# 3_ADC.net
KiCad netlist of a schematic drawn in Altium Designer
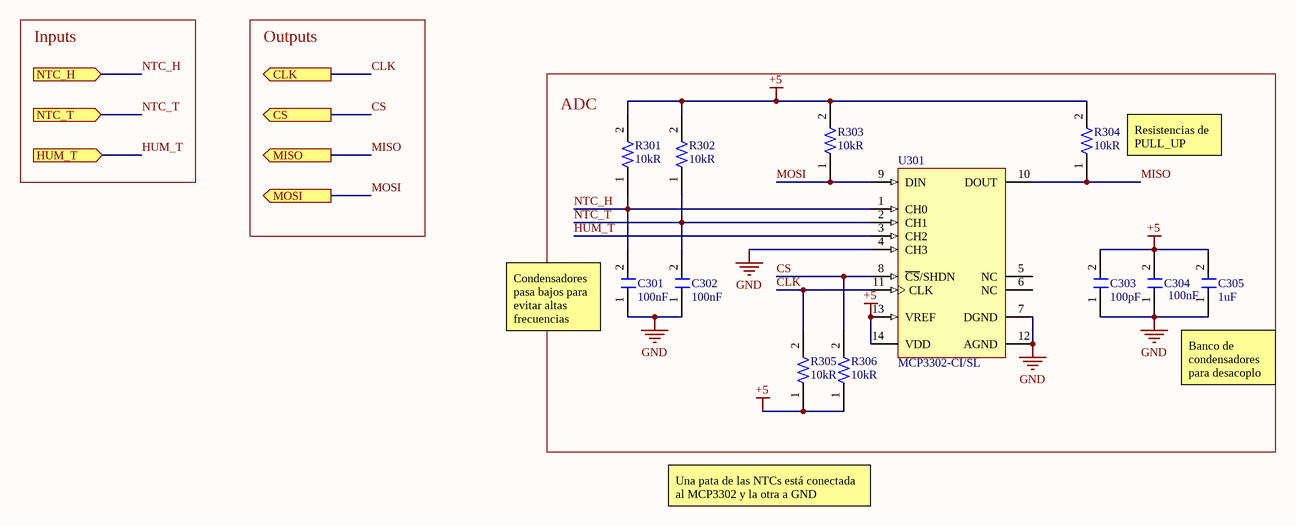
[diagram p0: [3] ADC.SchDoc]

(export (version "E")
  (design (tool "Eeschema 10.0.6"))
  (components
    (comp (ref "C301")
      (value "885012208058")
      (footprint "C1206FNPC-RW")
      (description "Cap Cer 0.1UF 25V X7R 1206")
      (fields
        (field (name "MANUFACTURER") "Wurth Electronics")
        (field (name "TOLERANCE") "10%")
        (field (name "CAPACITANCE") "100nF")
        (field (name ".CREATOR") "DO")
      )
      (libsource (lib "Passives") (part "C100n-25V-1206FNPC-X7R"))
    )
    (comp (ref "C302")
      (value "885012208058")
      (footprint "C1206FNPC-RW")
      (description "Cap Cer 0.1UF 25V X7R 1206")
      (fields
        (field (name "MANUFACTURER") "Wurth Electronics")
        (field (name "TOLERANCE") "10%")
        (field (name "CAPACITANCE") "100nF")
        (field (name ".CREATOR") "DO")
      )
      (libsource (lib "Passives") (part "C100n-25V-1206FNPC-X7R"))
    )
    (comp (ref "C303")
      (value "885012007057")
      (footprint "C0805FNPC-W")
      (fields
        (field (name "MANUFACTURER") "Wurth Electronics")
        (field (name "TOLERANCE") "5%")
        (field (name "CAPACITANCE") "100pF")
        (field (name ".CREATOR") "DR")
      )
      (libsource (lib "Passives") (part "C100p-50V-0805FNPC-C0G/NP0"))
    )
    (comp (ref "C304")
      (value "885012208058")
      (footprint "C1206FNPC-RW")
      (description "Cap Cer 0.1UF 25V X7R 1206")
      (fields
        (field (name "MANUFACTURER") "Wurth Electronics")
        (field (name "TOLERANCE") "10%")
        (field (name "CAPACITANCE") "100nF")
        (field (name ".CREATOR") "DO")
      )
      (libsource (lib "Passives") (part "C100n-25V-1206FNPC-X7R"))
    )
    (comp (ref "C305")
      (value "885012208036")
      (footprint "C1206FNPC-RW")
      (description "Cap Cer 1UF 16V X7R 1206")
      (fields
        (field (name "MANUFACTURER") "Wurth Electronics")
        (field (name "TOLERANCE") "10%")
        (field (name "CAPACITANCE") "1uF")
        (field (name ".CREATOR") "GP")
      )
      (libsource (lib "Passives") (part "C1u-16V-1206FNPC-X7R"))
    )
    (comp (ref "R301")
      (value "CRCW120610K0FKEA")
      (footprint "R1206FTK-W")
      (description "Res Thick Film 1206 10K Ohm 1% 0.25W(1/4W) +/-100ppm/ßC Pad SMD Automotive T/R")
      (fields (field (name "RESISTANCE") "10kR") (field (name ".CREATOR") "GP"))
      (libsource (lib "Passives") (part "R10k-1206FTK"))
    )
    (comp (ref "R302")
      (value "CRCW120610K0FKEA")
      (footprint "R1206FTK-W")
      (description "Res Thick Film 1206 10K Ohm 1% 0.25W(1/4W) +/-100ppm/ßC Pad SMD Automotive T/R")
      (fields (field (name "RESISTANCE") "10kR") (field (name ".CREATOR") "GP"))
      (libsource (lib "Passives") (part "R10k-1206FTK"))
    )
    (comp (ref "R303")
      (value "CRCW120610K0FKEA")
      (footprint "R1206FTK-W")
      (description "Res Thick Film 1206 10K Ohm 1% 0.25W(1/4W) +/-100ppm/ßC Pad SMD Automotive T/R")
      (fields (field (name "RESISTANCE") "10kR") (field (name ".CREATOR") "GP"))
      (libsource (lib "Passives") (part "R10k-1206FTK"))
    )
    (comp (ref "R304")
      (value "CRCW120610K0FKEA")
      (footprint "R1206FTK-W")
      (description "Res Thick Film 1206 10K Ohm 1% 0.25W(1/4W) +/-100ppm/ßC Pad SMD Automotive T/R")
      (fields (field (name "RESISTANCE") "10kR") (field (name ".CREATOR") "GP"))
      (libsource (lib "Passives") (part "R10k-1206FTK"))
    )
    (comp (ref "R305")
      (value "CRCW120610K0FKEA")
      (footprint "R1206FTK-W")
      (description "Res Thick Film 1206 10K Ohm 1% 0.25W(1/4W) +/-100ppm/ßC Pad SMD Automotive T/R")
      (fields (field (name "RESISTANCE") "10kR") (field (name ".CREATOR") "GP"))
      (libsource (lib "Passives") (part "R10k-1206FTK"))
    )
    (comp (ref "R306")
      (value "CRCW120610K0FKEA")
      (footprint "R1206FTK-W")
      (description "Res Thick Film 1206 10K Ohm 1% 0.25W(1/4W) +/-100ppm/ßC Pad SMD Automotive T/R")
      (fields (field (name "RESISTANCE") "10kR") (field (name ".CREATOR") "GP"))
      (libsource (lib "Passives") (part "R10k-1206FTK"))
    )
    (comp (ref "U301")
      (value "MCP3302-CI/SL")
      (footprint "SOIC-SL14_L")
      (description "ADC, Successive Approximation, 13-Bit, 1 Func, 4 Channel, Serial Access, PDSO14")
      (libsource (lib "EMEA- E-Tech Racing- I'Escola d'Enginyeria de Barcelona Est") (part "CON-ADC-MCP3004-14"))
    )
  )
  (nets
    (net (code "1") (name "+5") (class "Default")
      (node (ref "C303") (pin "2") (pinfunction "2_2") (pintype "passive"))
      (node (ref "C304") (pin "2") (pinfunction "2_2") (pintype "passive"))
      (node (ref "C305") (pin "2") (pinfunction "2_2") (pintype "passive"))
      (node (ref "R301") (pin "2") (pinfunction "2_2") (pintype "passive"))
      (node (ref "R302") (pin "2") (pinfunction "2_2") (pintype "passive"))
      (node (ref "R303") (pin "2") (pinfunction "2_2") (pintype "passive"))
      (node (ref "R304") (pin "2") (pinfunction "2_2") (pintype "passive"))
      (node (ref "R305") (pin "1") (pinfunction "1_1") (pintype "passive"))
      (node (ref "R306") (pin "1") (pinfunction "1_1") (pintype "passive"))
      (node (ref "U301") (pin "13") (pinfunction "VREF_13") (pintype "input"))
      (node (ref "U301") (pin "14") (pinfunction "VDD_14") (pintype "power_in"))
    )
    (net (code "2") (name "/CLK") (class "Default")
      (node (ref "R305") (pin "2") (pinfunction "2_2") (pintype "passive"))
      (node (ref "U301") (pin "11") (pinfunction "CLK_11") (pintype "input"))
    )
    (net (code "3") (name "/CS") (class "Default")
      (node (ref "R306") (pin "2") (pinfunction "2_2") (pintype "passive"))
      (node (ref "U301") (pin "8") (pinfunction "~{CS}/SHDN_8") (pintype "input"))
    )
    (net (code "4") (name "/HUM_T") (class "Default")
      (node (ref "U301") (pin "3") (pinfunction "CH2_3") (pintype "input"))
    )
    (net (code "5") (name "/MISO") (class "Default")
      (node (ref "R304") (pin "1") (pinfunction "1_1") (pintype "passive"))
      (node (ref "U301") (pin "10") (pinfunction "DOUT_10") (pintype "tri_state"))
    )
    (net (code "6") (name "/MOSI") (class "Default")
      (node (ref "R303") (pin "1") (pinfunction "1_1") (pintype "passive"))
      (node (ref "U301") (pin "9") (pinfunction "DIN_9") (pintype "input"))
    )
    (net (code "7") (name "/NTC_H") (class "Default")
      (node (ref "C301") (pin "2") (pinfunction "2_2") (pintype "passive"))
      (node (ref "R301") (pin "1") (pinfunction "1_1") (pintype "passive"))
      (node (ref "U301") (pin "1") (pinfunction "CH0_1") (pintype "input"))
    )
    (net (code "8") (name "/NTC_T") (class "Default")
      (node (ref "C302") (pin "2") (pinfunction "2_2") (pintype "passive"))
      (node (ref "R302") (pin "1") (pinfunction "1_1") (pintype "passive"))
      (node (ref "U301") (pin "2") (pinfunction "CH1_2") (pintype "input"))
    )
    (net (code "9") (name "GND") (class "Default")
      (node (ref "C301") (pin "1") (pinfunction "1_1") (pintype "passive"))
      (node (ref "C302") (pin "1") (pinfunction "1_1") (pintype "passive"))
      (node (ref "C303") (pin "1") (pinfunction "1_1") (pintype "passive"))
      (node (ref "C304") (pin "1") (pinfunction "1_1") (pintype "passive"))
      (node (ref "C305") (pin "1") (pinfunction "1_1") (pintype "passive"))
      (node (ref "U301") (pin "12") (pinfunction "AGND_12") (pintype "power_in"))
      (node (ref "U301") (pin "4") (pinfunction "CH3_4") (pintype "input"))
      (node (ref "U301") (pin "7") (pinfunction "DGND_7") (pintype "power_in"))
    )
    (net (code "10") (name "unconnected-(U301-NC-Pad5)") (class "Default")
      (node (ref "U301") (pin "5") (pinfunction "NC_5") (pintype "passive"))
    )
    (net (code "11") (name "unconnected-(U301-NC-Pad6)") (class "Default")
      (node (ref "U301") (pin "6") (pinfunction "NC_6") (pintype "passive"))
    )
  )
)
